# ADCIN_ACcoupled_WBC1-1.net
KiCad netlist of a schematic drawn in Altium Designer
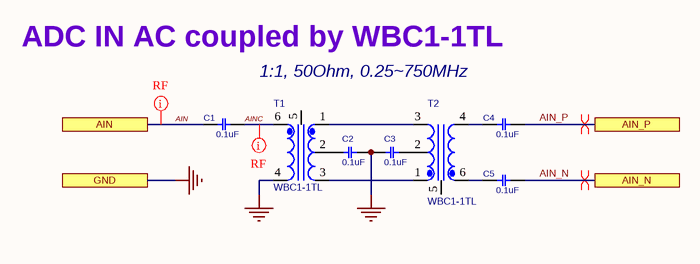
[diagram p0: ADCIN_ACcoupled_WBC1-1.SchDoc]

(export (version "E")
  (design (tool "Eeschema 10.0.6"))
  (components
    (comp (ref "C1")
      (value "0.1uF")
      (footprint "C0402")
      (description "CAP, MLCC")
      (fields (field (name "MANF_P#") "GRM155R61E104") (field (name "MANF") "Murata"))
      (libsource (lib "mlcc_smd_passive") (part "CAP_SMD_MLCC_100n50T"))
    )
    (comp (ref "C2")
      (value "0.1uF")
      (footprint "C0402")
      (description "CAP, MLCC")
      (fields (field (name "MANF_P#") "GRM155R61E104") (field (name "MANF") "Murata"))
      (libsource (lib "mlcc_smd_passive") (part "CAP_SMD_MLCC_100n50T"))
    )
    (comp (ref "C3")
      (value "0.1uF")
      (footprint "C0402")
      (description "CAP, MLCC")
      (fields (field (name "MANF_P#") "GRM155R61E104") (field (name "MANF") "Murata"))
      (libsource (lib "mlcc_smd_passive") (part "CAP_SMD_MLCC_100n50T"))
    )
    (comp (ref "C4")
      (value "0.1uF")
      (footprint "C0402")
      (description "CAP, MLCC")
      (fields (field (name "MANF_P#") "GRM155R61E104") (field (name "MANF") "Murata"))
      (libsource (lib "mlcc_smd_passive") (part "CAP_SMD_MLCC_100n50T"))
    )
    (comp (ref "C5")
      (value "0.1uF")
      (footprint "C0402")
      (description "CAP, MLCC")
      (fields (field (name "MANF_P#") "GRM155R61E104") (field (name "MANF") "Murata"))
      (libsource (lib "mlcc_smd_passive") (part "CAP_SMD_MLCC_100n50T"))
    )
    (comp (ref "T1")
      (value "WBC1-1TL")
      (footprint "TRNS150_6_450X420")
      (description "RF Transformer, 1:1, 50Ohm, 0.25~750MHz")
      (fields (field (name "MANF") "Coilcraft"))
      (libsource (lib "transformer_rf") (part "WBC1-1TL"))
    )
    (comp (ref "T2")
      (value "WBC1-1TL")
      (footprint "TRNS150_6_450X420")
      (description "RF Transformer, 1:1, 50Ohm, 0.25~750MHz")
      (fields (field (name "MANF") "Coilcraft"))
      (libsource (lib "transformer_rf") (part "WBC1-1TL"))
    )
  )
  (nets
    (net (code "1") (name "/AIN") (class "Default")
      (node (ref "C1") (pin "1") (pinfunction "1_1") (pintype "passive"))
    )
    (net (code "2") (name "/AINC") (class "Default")
      (node (ref "C1") (pin "2") (pinfunction "2_2") (pintype "passive"))
      (node (ref "T1") (pin "6") (pinfunction "SECDOT_6") (pintype "passive"))
    )
    (net (code "3") (name "/AIN_N") (class "Default")
      (node (ref "C5") (pin "2") (pinfunction "2_2") (pintype "passive"))
    )
    (net (code "4") (name "/AIN_P") (class "Default")
      (node (ref "C4") (pin "2") (pinfunction "2_2") (pintype "passive"))
    )
    (net (code "5") (name "GND") (class "Default")
      (node (ref "C2") (pin "2") (pinfunction "2_2") (pintype "passive"))
      (node (ref "C3") (pin "1") (pinfunction "1_1") (pintype "passive"))
      (node (ref "T1") (pin "4") (pinfunction "SEC_4") (pintype "passive"))
    )
    (net (code "6") (name "Net-(T1-PRI)") (class "Default")
      (node (ref "T1") (pin "3") (pinfunction "PRI_3") (pintype "passive"))
      (node (ref "T2") (pin "1") (pinfunction "PRIDOT_1") (pintype "passive"))
    )
    (net (code "7") (name "Net-(T1-PRICT)") (class "Default")
      (node (ref "C2") (pin "1") (pinfunction "1_1") (pintype "passive"))
      (node (ref "T1") (pin "2") (pinfunction "PRICT_2") (pintype "passive"))
    )
    (net (code "8") (name "Net-(T1-PRIDOT)") (class "Default")
      (node (ref "T1") (pin "1") (pinfunction "PRIDOT_1") (pintype "passive"))
      (node (ref "T2") (pin "3") (pinfunction "PRI_3") (pintype "passive"))
    )
    (net (code "9") (name "Net-(T2-PRICT)") (class "Default")
      (node (ref "C3") (pin "2") (pinfunction "2_2") (pintype "passive"))
      (node (ref "T2") (pin "2") (pinfunction "PRICT_2") (pintype "passive"))
    )
    (net (code "10") (name "Net-(T2-SEC)") (class "Default")
      (node (ref "C4") (pin "1") (pinfunction "1_1") (pintype "passive"))
      (node (ref "T2") (pin "4") (pinfunction "SEC_4") (pintype "passive"))
    )
    (net (code "11") (name "Net-(T2-SECDOT)") (class "Default")
      (node (ref "C5") (pin "1") (pinfunction "1_1") (pintype "passive"))
      (node (ref "T2") (pin "6") (pinfunction "SECDOT_6") (pintype "passive"))
    )
    (net (code "12") (name "unconnected-(T1-NC-Pad5)") (class "Default")
      (node (ref "T1") (pin "5") (pinfunction "NC_5") (pintype "passive"))
    )
    (net (code "13") (name "unconnected-(T2-NC-Pad5)") (class "Default")
      (node (ref "T2") (pin "5") (pinfunction "NC_5") (pintype "passive"))
    )
  )
)
